# cpuPowerAndJtag.net
KiCad netlist of a schematic drawn in Altium Designer
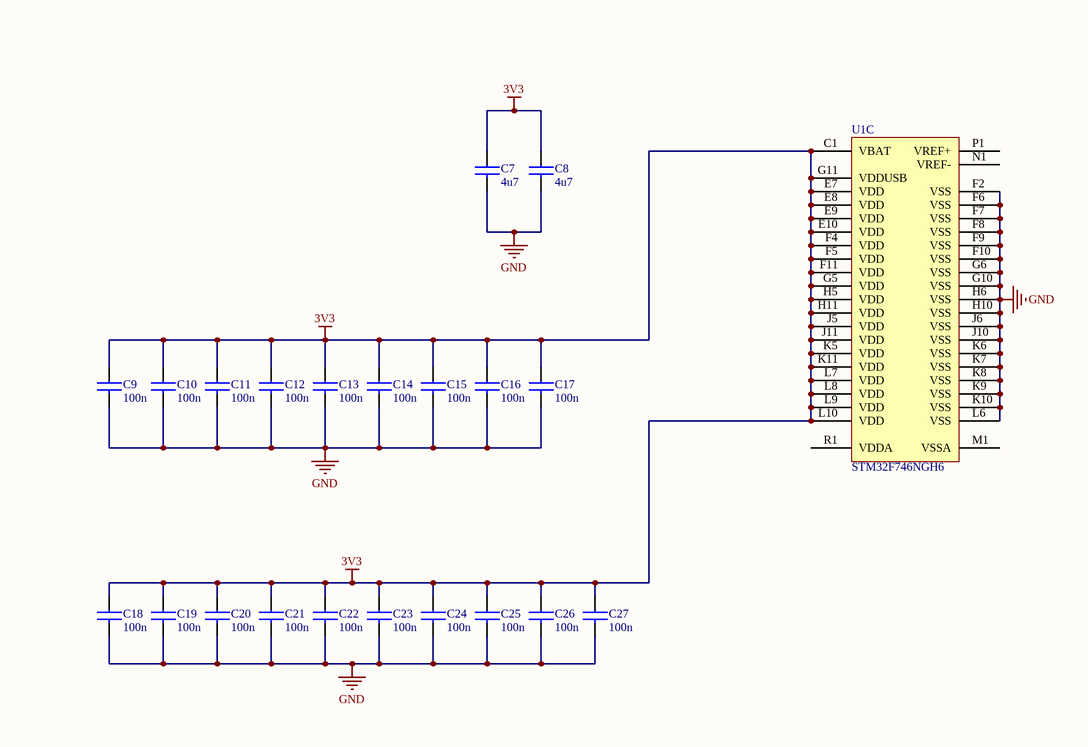
[diagram p0: cpuPowerAndJtag.SchDoc, bottom right]

(export (version "E")
  (design (tool "Eeschema 10.0.6"))
  (components
    (comp (ref "C7")
      (value "4u7")
      (footprint "C0402")
      (description "CAP CER 4.7UF 10V 20% X5R 0402")
      (fields
        (field (name "MANUFACTURER") "TDK Corporation")
        (field (name "MANUFACTURER PART NUMBER") "C1005X5R1A475M")
        (field (name ".CHECKED PCB") "RF")
        (field (name ".CHECKED SCH") "RF")
      )
      (libsource (lib "iMX6_Rex_Development_Baseboard_V1I1") (part "C1005X5R1A475M"))
    )
    (comp (ref "C8")
      (value "4u7")
      (footprint "C0402")
      (description "CAP CER 4.7UF 10V 20% X5R 0402")
      (fields
        (field (name "MANUFACTURER") "TDK Corporation")
        (field (name "MANUFACTURER PART NUMBER") "C1005X5R1A475M")
        (field (name ".CHECKED PCB") "RF")
        (field (name ".CHECKED SCH") "RF")
      )
      (libsource (lib "iMX6_Rex_Development_Baseboard_V1I1") (part "C1005X5R1A475M"))
    )
    (comp (ref "C9")
      (value "100n")
      (footprint "C0402")
      (description "CAP CER .10UF 50V X5R 10% 0402")
      (fields
        (field (name "MANUFACTURER") "TDK Corporation")
        (field (name "MANUFACTURER PART NUMBER") "C1005X5R1H104K")
      )
      (libsource (lib "iMX6_Rex_Development_Baseboard_V1I1") (part "C1005X5R1H104K"))
    )
    (comp (ref "C10")
      (value "100n")
      (footprint "C0402")
      (description "CAP CER .10UF 50V X5R 10% 0402")
      (fields
        (field (name "MANUFACTURER") "TDK Corporation")
        (field (name "MANUFACTURER PART NUMBER") "C1005X5R1H104K")
      )
      (libsource (lib "iMX6_Rex_Development_Baseboard_V1I1") (part "C1005X5R1H104K"))
    )
    (comp (ref "C11")
      (value "100n")
      (footprint "C0402")
      (description "CAP CER .10UF 50V X5R 10% 0402")
      (fields
        (field (name "MANUFACTURER") "TDK Corporation")
        (field (name "MANUFACTURER PART NUMBER") "C1005X5R1H104K")
      )
      (libsource (lib "iMX6_Rex_Development_Baseboard_V1I1") (part "C1005X5R1H104K"))
    )
    (comp (ref "C12")
      (value "100n")
      (footprint "C0402")
      (description "CAP CER .10UF 50V X5R 10% 0402")
      (fields
        (field (name "MANUFACTURER") "TDK Corporation")
        (field (name "MANUFACTURER PART NUMBER") "C1005X5R1H104K")
      )
      (libsource (lib "iMX6_Rex_Development_Baseboard_V1I1") (part "C1005X5R1H104K"))
    )
    (comp (ref "C13")
      (value "100n")
      (footprint "C0402")
      (description "CAP CER .10UF 50V X5R 10% 0402")
      (fields
        (field (name "MANUFACTURER") "TDK Corporation")
        (field (name "MANUFACTURER PART NUMBER") "C1005X5R1H104K")
      )
      (libsource (lib "iMX6_Rex_Development_Baseboard_V1I1") (part "C1005X5R1H104K"))
    )
    (comp (ref "C14")
      (value "100n")
      (footprint "C0402")
      (description "CAP CER .10UF 50V X5R 10% 0402")
      (fields
        (field (name "MANUFACTURER") "TDK Corporation")
        (field (name "MANUFACTURER PART NUMBER") "C1005X5R1H104K")
      )
      (libsource (lib "iMX6_Rex_Development_Baseboard_V1I1") (part "C1005X5R1H104K"))
    )
    (comp (ref "C15")
      (value "100n")
      (footprint "C0402")
      (description "CAP CER .10UF 50V X5R 10% 0402")
      (fields
        (field (name "MANUFACTURER") "TDK Corporation")
        (field (name "MANUFACTURER PART NUMBER") "C1005X5R1H104K")
      )
      (libsource (lib "iMX6_Rex_Development_Baseboard_V1I1") (part "C1005X5R1H104K"))
    )
    (comp (ref "C16")
      (value "100n")
      (footprint "C0402")
      (description "CAP CER .10UF 50V X5R 10% 0402")
      (fields
        (field (name "MANUFACTURER") "TDK Corporation")
        (field (name "MANUFACTURER PART NUMBER") "C1005X5R1H104K")
      )
      (libsource (lib "iMX6_Rex_Development_Baseboard_V1I1") (part "C1005X5R1H104K"))
    )
    (comp (ref "C17")
      (value "100n")
      (footprint "C0402")
      (description "CAP CER .10UF 50V X5R 10% 0402")
      (fields
        (field (name "MANUFACTURER") "TDK Corporation")
        (field (name "MANUFACTURER PART NUMBER") "C1005X5R1H104K")
      )
      (libsource (lib "iMX6_Rex_Development_Baseboard_V1I1") (part "C1005X5R1H104K"))
    )
    (comp (ref "C18")
      (value "100n")
      (footprint "C0402")
      (description "CAP CER .10UF 50V X5R 10% 0402")
      (fields
        (field (name "MANUFACTURER") "TDK Corporation")
        (field (name "MANUFACTURER PART NUMBER") "C1005X5R1H104K")
      )
      (libsource (lib "iMX6_Rex_Development_Baseboard_V1I1") (part "C1005X5R1H104K"))
    )
    (comp (ref "C19")
      (value "100n")
      (footprint "C0402")
      (description "CAP CER .10UF 50V X5R 10% 0402")
      (fields
        (field (name "MANUFACTURER") "TDK Corporation")
        (field (name "MANUFACTURER PART NUMBER") "C1005X5R1H104K")
      )
      (libsource (lib "iMX6_Rex_Development_Baseboard_V1I1") (part "C1005X5R1H104K"))
    )
    (comp (ref "C20")
      (value "100n")
      (footprint "C0402")
      (description "CAP CER .10UF 50V X5R 10% 0402")
      (fields
        (field (name "MANUFACTURER") "TDK Corporation")
        (field (name "MANUFACTURER PART NUMBER") "C1005X5R1H104K")
      )
      (libsource (lib "iMX6_Rex_Development_Baseboard_V1I1") (part "C1005X5R1H104K"))
    )
    (comp (ref "C21")
      (value "100n")
      (footprint "C0402")
      (description "CAP CER .10UF 50V X5R 10% 0402")
      (fields
        (field (name "MANUFACTURER") "TDK Corporation")
        (field (name "MANUFACTURER PART NUMBER") "C1005X5R1H104K")
      )
      (libsource (lib "iMX6_Rex_Development_Baseboard_V1I1") (part "C1005X5R1H104K"))
    )
    (comp (ref "C22")
      (value "100n")
      (footprint "C0402")
      (description "CAP CER .10UF 50V X5R 10% 0402")
      (fields
        (field (name "MANUFACTURER") "TDK Corporation")
        (field (name "MANUFACTURER PART NUMBER") "C1005X5R1H104K")
      )
      (libsource (lib "iMX6_Rex_Development_Baseboard_V1I1") (part "C1005X5R1H104K"))
    )
    (comp (ref "C23")
      (value "100n")
      (footprint "C0402")
      (description "CAP CER .10UF 50V X5R 10% 0402")
      (fields
        (field (name "MANUFACTURER") "TDK Corporation")
        (field (name "MANUFACTURER PART NUMBER") "C1005X5R1H104K")
      )
      (libsource (lib "iMX6_Rex_Development_Baseboard_V1I1") (part "C1005X5R1H104K"))
    )
    (comp (ref "C24")
      (value "100n")
      (footprint "C0402")
      (description "CAP CER .10UF 50V X5R 10% 0402")
      (fields
        (field (name "MANUFACTURER") "TDK Corporation")
        (field (name "MANUFACTURER PART NUMBER") "C1005X5R1H104K")
      )
      (libsource (lib "iMX6_Rex_Development_Baseboard_V1I1") (part "C1005X5R1H104K"))
    )
    (comp (ref "C25")
      (value "100n")
      (footprint "C0402")
      (description "CAP CER .10UF 50V X5R 10% 0402")
      (fields
        (field (name "MANUFACTURER") "TDK Corporation")
        (field (name "MANUFACTURER PART NUMBER") "C1005X5R1H104K")
      )
      (libsource (lib "iMX6_Rex_Development_Baseboard_V1I1") (part "C1005X5R1H104K"))
    )
    (comp (ref "C26")
      (value "100n")
      (footprint "C0402")
      (description "CAP CER .10UF 50V X5R 10% 0402")
      (fields
        (field (name "MANUFACTURER") "TDK Corporation")
        (field (name "MANUFACTURER PART NUMBER") "C1005X5R1H104K")
      )
      (libsource (lib "iMX6_Rex_Development_Baseboard_V1I1") (part "C1005X5R1H104K"))
    )
    (comp (ref "C27")
      (value "100n")
      (footprint "C0402")
      (description "CAP CER .10UF 50V X5R 10% 0402")
      (fields
        (field (name "MANUFACTURER") "TDK Corporation")
        (field (name "MANUFACTURER PART NUMBER") "C1005X5R1H104K")
      )
      (libsource (lib "iMX6_Rex_Development_Baseboard_V1I1") (part "C1005X5R1H104K"))
    )
    (comp (ref "U1")
      (value "STM32F746NGH6")
      (footprint "STM-TFBGA216")
      (fields (field (name "PARTNUMBER") "STM32F746NG"))
      (libsource (lib "stm32f746ng") (part "STM32F746NGH6"))
    )
  )
  (nets
    (net (code "1") (name "3V3") (class "Default")
      (node (ref "C10") (pin "1") (pinfunction "1_1") (pintype "passive"))
      (node (ref "C11") (pin "1") (pinfunction "1_1") (pintype "passive"))
      (node (ref "C12") (pin "1") (pinfunction "1_1") (pintype "passive"))
      (node (ref "C13") (pin "1") (pinfunction "1_1") (pintype "passive"))
      (node (ref "C14") (pin "1") (pinfunction "1_1") (pintype "passive"))
      (node (ref "C15") (pin "1") (pinfunction "1_1") (pintype "passive"))
      (node (ref "C16") (pin "1") (pinfunction "1_1") (pintype "passive"))
      (node (ref "C17") (pin "1") (pinfunction "1_1") (pintype "passive"))
      (node (ref "C18") (pin "1") (pinfunction "1_1") (pintype "passive"))
      (node (ref "C19") (pin "1") (pinfunction "1_1") (pintype "passive"))
      (node (ref "C20") (pin "1") (pinfunction "1_1") (pintype "passive"))
      (node (ref "C21") (pin "1") (pinfunction "1_1") (pintype "passive"))
      (node (ref "C22") (pin "1") (pinfunction "1_1") (pintype "passive"))
      (node (ref "C23") (pin "1") (pinfunction "1_1") (pintype "passive"))
      (node (ref "C24") (pin "1") (pinfunction "1_1") (pintype "passive"))
      (node (ref "C25") (pin "1") (pinfunction "1_1") (pintype "passive"))
      (node (ref "C26") (pin "1") (pinfunction "1_1") (pintype "passive"))
      (node (ref "C27") (pin "1") (pinfunction "1_1") (pintype "passive"))
      (node (ref "C7") (pin "1") (pinfunction "1_1") (pintype "passive"))
      (node (ref "C8") (pin "1") (pinfunction "1_1") (pintype "passive"))
      (node (ref "C9") (pin "1") (pinfunction "1_1") (pintype "passive"))
      (node (ref "U1") (pin "C1") (pinfunction "VBAT_C1") (pintype "power_in"))
      (node (ref "U1") (pin "E10") (pinfunction "VDD_E10") (pintype "power_in"))
      (node (ref "U1") (pin "E7") (pinfunction "VDD_E7") (pintype "power_in"))
      (node (ref "U1") (pin "E8") (pinfunction "VDD_E8") (pintype "power_in"))
      (node (ref "U1") (pin "E9") (pinfunction "VDD_E9") (pintype "power_in"))
      (node (ref "U1") (pin "F11") (pinfunction "VDD_F11") (pintype "power_in"))
      (node (ref "U1") (pin "F4") (pinfunction "VDD_F4") (pintype "power_in"))
      (node (ref "U1") (pin "F5") (pinfunction "VDD_F5") (pintype "power_in"))
      (node (ref "U1") (pin "G11") (pinfunction "VDDUSB_G11") (pintype "power_in"))
      (node (ref "U1") (pin "G5") (pinfunction "VDD_G5") (pintype "power_in"))
      (node (ref "U1") (pin "H11") (pinfunction "VDD_H11") (pintype "power_in"))
      (node (ref "U1") (pin "H5") (pinfunction "VDD_H5") (pintype "power_in"))
      (node (ref "U1") (pin "J11") (pinfunction "VDD_J11") (pintype "power_in"))
      (node (ref "U1") (pin "J5") (pinfunction "VDD_J5") (pintype "power_in"))
      (node (ref "U1") (pin "K11") (pinfunction "VDD_K11") (pintype "power_in"))
      (node (ref "U1") (pin "K5") (pinfunction "VDD_K5") (pintype "power_in"))
      (node (ref "U1") (pin "L10") (pinfunction "VDD_L10") (pintype "power_in"))
      (node (ref "U1") (pin "L7") (pinfunction "VDD_L7") (pintype "power_in"))
      (node (ref "U1") (pin "L8") (pinfunction "VDD_L8") (pintype "power_in"))
      (node (ref "U1") (pin "L9") (pinfunction "VDD_L9") (pintype "power_in"))
    )
    (net (code "2") (name "GND") (class "Default")
      (node (ref "C10") (pin "2") (pinfunction "2_2") (pintype "passive"))
      (node (ref "C11") (pin "2") (pinfunction "2_2") (pintype "passive"))
      (node (ref "C12") (pin "2") (pinfunction "2_2") (pintype "passive"))
      (node (ref "C13") (pin "2") (pinfunction "2_2") (pintype "passive"))
      (node (ref "C14") (pin "2") (pinfunction "2_2") (pintype "passive"))
      (node (ref "C15") (pin "2") (pinfunction "2_2") (pintype "passive"))
      (node (ref "C16") (pin "2") (pinfunction "2_2") (pintype "passive"))
      (node (ref "C17") (pin "2") (pinfunction "2_2") (pintype "passive"))
      (node (ref "C18") (pin "2") (pinfunction "2_2") (pintype "passive"))
      (node (ref "C19") (pin "2") (pinfunction "2_2") (pintype "passive"))
      (node (ref "C20") (pin "2") (pinfunction "2_2") (pintype "passive"))
      (node (ref "C21") (pin "2") (pinfunction "2_2") (pintype "passive"))
      (node (ref "C22") (pin "2") (pinfunction "2_2") (pintype "passive"))
      (node (ref "C23") (pin "2") (pinfunction "2_2") (pintype "passive"))
      (node (ref "C24") (pin "2") (pinfunction "2_2") (pintype "passive"))
      (node (ref "C25") (pin "2") (pinfunction "2_2") (pintype "passive"))
      (node (ref "C26") (pin "2") (pinfunction "2_2") (pintype "passive"))
      (node (ref "C27") (pin "2") (pinfunction "2_2") (pintype "passive"))
      (node (ref "C7") (pin "2") (pinfunction "2_2") (pintype "passive"))
      (node (ref "C8") (pin "2") (pinfunction "2_2") (pintype "passive"))
      (node (ref "C9") (pin "2") (pinfunction "2_2") (pintype "passive"))
      (node (ref "U1") (pin "F10") (pinfunction "VSS_F10") (pintype "power_in"))
      (node (ref "U1") (pin "F2") (pinfunction "VSS_F2") (pintype "power_in"))
      (node (ref "U1") (pin "F6") (pinfunction "VSS_F6") (pintype "power_in"))
      (node (ref "U1") (pin "F7") (pinfunction "VSS_F7") (pintype "power_in"))
      (node (ref "U1") (pin "F8") (pinfunction "VSS_F8") (pintype "power_in"))
      (node (ref "U1") (pin "F9") (pinfunction "VSS_F9") (pintype "power_in"))
      (node (ref "U1") (pin "G10") (pinfunction "VSS_G10") (pintype "power_in"))
      (node (ref "U1") (pin "G6") (pinfunction "VSS_G6") (pintype "power_in"))
      (node (ref "U1") (pin "H10") (pinfunction "VSS_H10") (pintype "power_in"))
      (node (ref "U1") (pin "H6") (pinfunction "VSS_H6") (pintype "power_in"))
      (node (ref "U1") (pin "J10") (pinfunction "VSS_J10") (pintype "power_in"))
      (node (ref "U1") (pin "J6") (pinfunction "VSS_J6") (pintype "power_in"))
      (node (ref "U1") (pin "K10") (pinfunction "VSS_K10") (pintype "power_in"))
      (node (ref "U1") (pin "K6") (pinfunction "VSS_K6") (pintype "power_in"))
      (node (ref "U1") (pin "K7") (pinfunction "VSS_K7") (pintype "power_in"))
      (node (ref "U1") (pin "K8") (pinfunction "VSS_K8") (pintype "power_in"))
      (node (ref "U1") (pin "K9") (pinfunction "VSS_K9") (pintype "power_in"))
      (node (ref "U1") (pin "L6") (pinfunction "VSS_L6") (pintype "power_in"))
    )
    (net (code "3") (name "unconnected-(U1C-VDDA-PadR1)") (class "Default")
      (node (ref "U1") (pin "R1") (pinfunction "VDDA_R1") (pintype "power_in"))
    )
    (net (code "4") (name "unconnected-(U1C-VREF+-PadP1)") (class "Default")
      (node (ref "U1") (pin "P1") (pinfunction "VREF+_P1") (pintype "power_in"))
    )
    (net (code "5") (name "unconnected-(U1C-VREF--PadN1)") (class "Default")
      (node (ref "U1") (pin "N1") (pinfunction "VREF-_N1") (pintype "power_in"))
    )
    (net (code "6") (name "unconnected-(U1C-VSSA-PadM1)") (class "Default")
      (node (ref "U1") (pin "M1") (pinfunction "VSSA_M1") (pintype "power_in"))
    )
  )
)
